# HH1D.net
KiCad netlist of a schematic drawn in EAGLE
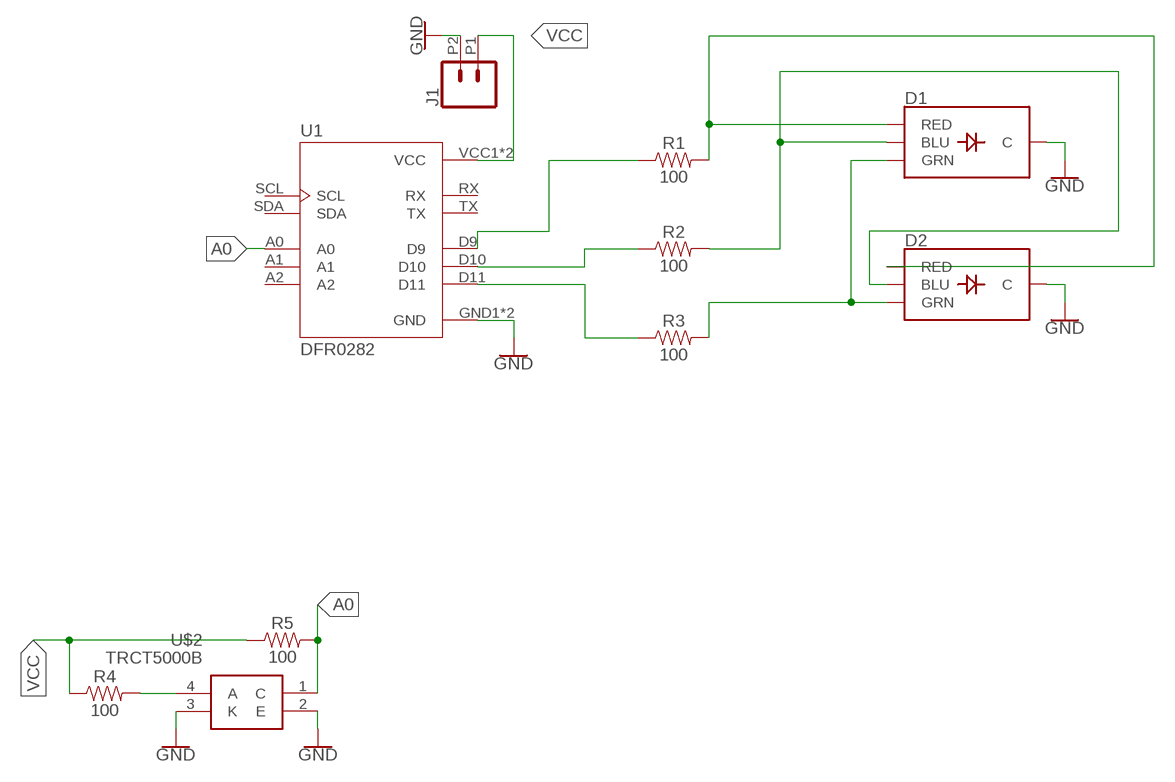
[diagram p0: schematic, sheet 1]

(export (version "E")
  (design (tool "Eeschema 10.0.6"))
  (components
    (comp (ref "D1")
      (value "LED-RGB-CCPIRANHA")
      (footprint "eagle-import:LED_PIRANHA_5MM")
      (libsource (lib "eagle-import") (part "LED-RGB-CCPIRANHA"))
    )
    (comp (ref "D2")
      (value "LED-RGB-CCPIRANHA")
      (footprint "eagle-import:LED_PIRANHA_5MM")
      (libsource (lib "eagle-import") (part "LED-RGB-CCPIRANHA"))
    )
    (comp (ref "J1")
      (value "CONN_022.54MM_SCREWTERM")
      (footprint "eagle-import:1X02_2.54_SCREWTERM")
      (libsource (lib "eagle-import") (part "CONN_022.54MM_SCREWTERM"))
    )
    (comp (ref "R1")
      (value "100")
      (footprint "eagle-import:AXIAL-0.3")
      (libsource (lib "eagle-import") (part "100OHM-HORIZ-1/4W-1%"))
    )
    (comp (ref "R2")
      (value "100")
      (footprint "eagle-import:AXIAL-0.3")
      (libsource (lib "eagle-import") (part "100OHM-HORIZ-1/4W-1%"))
    )
    (comp (ref "R3")
      (value "100")
      (footprint "eagle-import:AXIAL-0.3")
      (libsource (lib "eagle-import") (part "100OHM-HORIZ-1/4W-1%"))
    )
    (comp (ref "R4")
      (value "100")
      (footprint "eagle-import:AXIAL-0.3")
      (libsource (lib "eagle-import") (part "100OHM-HORIZ-1/4W-1%"))
    )
    (comp (ref "R5")
      (value "100")
      (footprint "eagle-import:AXIAL-0.3")
      (libsource (lib "eagle-import") (part "100OHM-HORIZ-1/4W-1%"))
    )
    (comp (ref "U$2")
      (value "TRCT5000B")
      (footprint "eagle-import:TRCT5000B")
      (libsource (lib "eagle-import") (part "TRCT5000B"))
    )
    (comp (ref "U1")
      (value "DFR0282")
      (footprint "eagle-import:MODULE_DFR0282")
      (fields (field (name "MF") "DFRobot"))
      (libsource (lib "eagle-import") (part "DFR0282"))
    )
  )
  (nets
    (net (code "1") (name "A0") (class "Default")
      (node (ref "R5") (pin "P$2") (pinfunction "2_P$2") (pintype "passive"))
      (node (ref "U$2") (pin "1") (pinfunction "C_1") (pintype "bidirectional"))
      (node (ref "U1") (pin "A0") (pinfunction "A0_A0") (pintype "bidirectional"))
    )
    (net (code "2") (name "GND") (class "Default")
      (node (ref "D1") (pin "-") (pinfunction "C_-") (pintype "bidirectional"))
      (node (ref "D2") (pin "-") (pinfunction "C_-") (pintype "bidirectional"))
      (node (ref "J1") (pin "P2") (pinfunction "2_P2") (pintype "passive"))
      (node (ref "U$2") (pin "2") (pinfunction "E_2") (pintype "bidirectional"))
      (node (ref "U$2") (pin "3") (pinfunction "K_3") (pintype "bidirectional"))
      (node (ref "U1") (pin "GND1") (pinfunction "GND_GND1") (pintype "power_in"))
      (node (ref "U1") (pin "GND2") (pinfunction "GND_GND2") (pintype "power_in"))
    )
    (net (code "3") (name "Net-(D1-BLU)") (class "Default")
      (node (ref "D1") (pin "B") (pinfunction "BLU_B") (pintype "bidirectional"))
      (node (ref "D2") (pin "B") (pinfunction "BLU_B") (pintype "bidirectional"))
      (node (ref "R2") (pin "P$2") (pinfunction "2_P$2") (pintype "passive"))
    )
    (net (code "4") (name "Net-(D1-GRN)") (class "Default")
      (node (ref "D1") (pin "G") (pinfunction "GRN_G") (pintype "bidirectional"))
      (node (ref "D2") (pin "G") (pinfunction "GRN_G") (pintype "bidirectional"))
      (node (ref "R3") (pin "P$2") (pinfunction "2_P$2") (pintype "passive"))
    )
    (net (code "5") (name "Net-(D1-RED)") (class "Default")
      (node (ref "D1") (pin "R") (pinfunction "RED_R") (pintype "bidirectional"))
      (node (ref "D2") (pin "R") (pinfunction "RED_R") (pintype "bidirectional"))
      (node (ref "R1") (pin "P$2") (pinfunction "2_P$2") (pintype "passive"))
    )
    (net (code "6") (name "Net-(R1-1)") (class "Default")
      (node (ref "R1") (pin "P$1") (pinfunction "1_P$1") (pintype "passive"))
      (node (ref "U1") (pin "D9") (pinfunction "D9_D9") (pintype "bidirectional"))
    )
    (net (code "7") (name "Net-(R2-1)") (class "Default")
      (node (ref "R2") (pin "P$1") (pinfunction "1_P$1") (pintype "passive"))
      (node (ref "U1") (pin "D10") (pinfunction "D10_D10") (pintype "bidirectional"))
    )
    (net (code "8") (name "Net-(R3-1)") (class "Default")
      (node (ref "R3") (pin "P$1") (pinfunction "1_P$1") (pintype "passive"))
      (node (ref "U1") (pin "D11") (pinfunction "D11_D11") (pintype "bidirectional"))
    )
    (net (code "9") (name "Net-(R4-2)") (class "Default")
      (node (ref "R4") (pin "P$2") (pinfunction "2_P$2") (pintype "passive"))
      (node (ref "U$2") (pin "4") (pinfunction "A_4") (pintype "bidirectional"))
    )
    (net (code "10") (name "VCC") (class "Default")
      (node (ref "J1") (pin "P1") (pinfunction "1_P1") (pintype "passive"))
      (node (ref "R4") (pin "P$1") (pinfunction "1_P$1") (pintype "passive"))
      (node (ref "R5") (pin "P$1") (pinfunction "1_P$1") (pintype "passive"))
      (node (ref "U1") (pin "VCC1") (pinfunction "VCC_VCC1") (pintype "power_in"))
      (node (ref "U1") (pin "VCC2") (pinfunction "VCC_VCC2") (pintype "power_in"))
    )
    (net (code "11") (name "unconnected-(U1-PadA1)") (class "Default")
      (node (ref "U1") (pin "A1") (pinfunction "A1_A1") (pintype "bidirectional"))
    )
    (net (code "12") (name "unconnected-(U1-PadA2)") (class "Default")
      (node (ref "U1") (pin "A2") (pinfunction "A2_A2") (pintype "bidirectional"))
    )
    (net (code "13") (name "unconnected-(U1-PadRX)") (class "Default")
      (node (ref "U1") (pin "RX") (pinfunction "RX_RX") (pintype "input"))
    )
    (net (code "14") (name "unconnected-(U1-PadSCL)") (class "Default")
      (node (ref "U1") (pin "SCL") (pinfunction "SCL_SCL") (pintype "input"))
    )
    (net (code "15") (name "unconnected-(U1-PadSDA)") (class "Default")
      (node (ref "U1") (pin "SDA") (pinfunction "SDA_SDA") (pintype "bidirectional"))
    )
    (net (code "16") (name "unconnected-(U1-PadTX)") (class "Default")
      (node (ref "U1") (pin "TX") (pinfunction "TX_TX") (pintype "output"))
    )
  )
)
